# 11_-_Power_Input_and_Regulators.net
KiCad netlist of a schematic drawn in Altium Designer
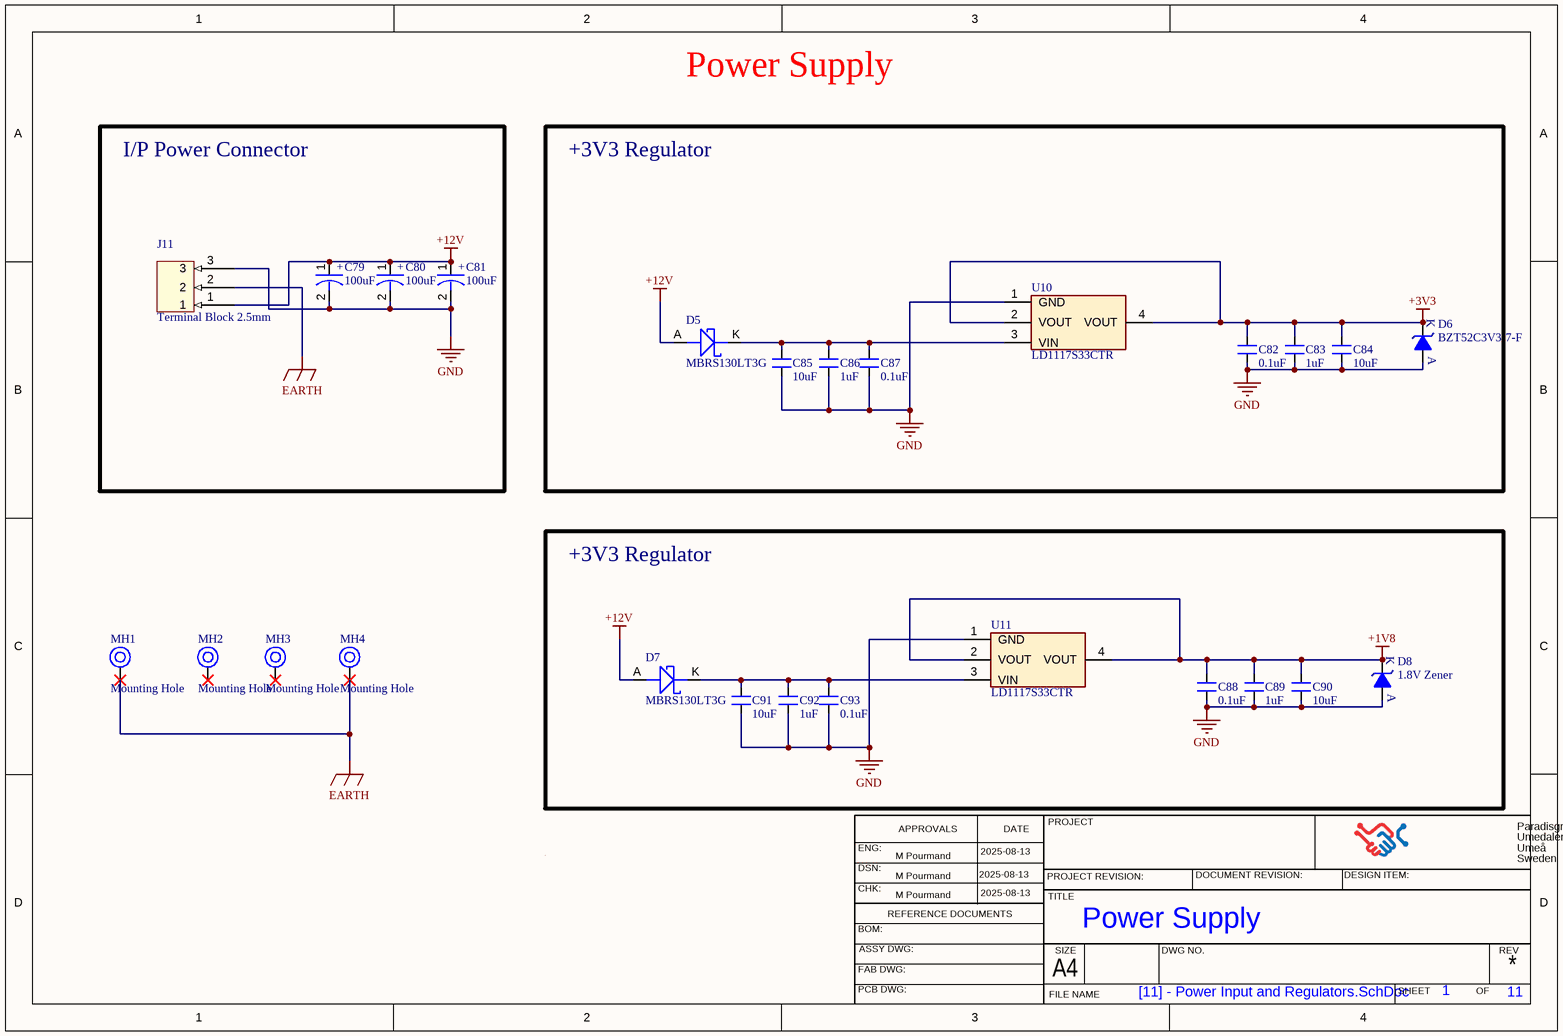
[diagram p0: [11] - Power Input and Regulators.SchDoc]

(export (version "E")
  (design (tool "Eeschema 10.0.6"))
  (components
    (comp (ref "C79")
      (value "100uF")
      (footprint "ACAP_P305_D393_H393_RAD")
      (description "100µF 50V Aluminum Polymer Capacitor Radial, Can - SMD 28mOhm 4000 Hrs @ 125°C")
      (fields
        (field (name "MANUFACTURER") "Nichicon")
        (field (name "MANUFACTURER PART NUMBER") "GYA1H101MCQ1GS")
      )
      (libsource (lib "ESTEEMPCBLIB") (part "CAP-P_100uF-50V-20%-RAD"))
    )
    (comp (ref "C80")
      (value "100uF")
      (footprint "ACAP_P305_D393_H393_RAD")
      (description "100µF 50V Aluminum Polymer Capacitor Radial, Can - SMD 28mOhm 4000 Hrs @ 125°C")
      (fields
        (field (name "MANUFACTURER") "Nichicon")
        (field (name "MANUFACTURER PART NUMBER") "GYA1H101MCQ1GS")
      )
      (libsource (lib "ESTEEMPCBLIB") (part "CAP-P_100uF-50V-20%-RAD"))
    )
    (comp (ref "C81")
      (value "100uF")
      (footprint "ACAP_P305_D393_H393_RAD")
      (description "100µF 50V Aluminum Polymer Capacitor Radial, Can - SMD 28mOhm 4000 Hrs @ 125°C")
      (fields
        (field (name "MANUFACTURER") "Nichicon")
        (field (name "MANUFACTURER PART NUMBER") "GYA1H101MCQ1GS")
      )
      (libsource (lib "ESTEEMPCBLIB") (part "CAP-P_100uF-50V-20%-RAD"))
    )
    (comp (ref "C82")
      (value "0.1uF")
      (footprint "CAP_0805")
      (description "0.1µF ±10% 50V Ceramic Capacitor X7R 0805 (2012 Metric)")
      (fields
        (field (name "MANUFACTURER") "Samsung")
        (field (name "MANUFACTURER PART NUMBER") "CL21B104KBCNNNC")
      )
      (libsource (lib "ESTEEMPCBLIB") (part "CAP_0.1uF-50V-10%-0805"))
    )
    (comp (ref "C83")
      (value "1uF")
      (footprint "CAP_0805")
      (description "1µF ±5% 50V Ceramic Capacitor X7R 0805 (2012 Metric)")
      (fields
        (field (name "MANUFACTURER") "Samsung")
        (field (name "MANUFACTURER PART NUMBER") "CC0805JKX7R9BB105")
      )
      (libsource (lib "ESTEEMPCBLIB") (part "CAP_1uF-50V-5%-0805"))
    )
    (comp (ref "C84")
      (value "10uF")
      (footprint "CAP_1206")
      (description "10µF ±10% 50V Ceramic Capacitor X7R 1206 (3216 Metric)")
      (fields
        (field (name "MANUFACTURER") "KEMET")
        (field (name "MANUFACTURER PART NUMBER") "CL31B106KBHNNNE")
      )
      (libsource (lib "ESTEEMPCBLIB") (part "CAP_10uF-50V-10%-1206"))
    )
    (comp (ref "C85")
      (value "10uF")
      (footprint "CAP_1206")
      (description "10µF ±10% 50V Ceramic Capacitor X7R 1206 (3216 Metric)")
      (fields
        (field (name "MANUFACTURER") "KEMET")
        (field (name "MANUFACTURER PART NUMBER") "CL31B106KBHNNNE")
      )
      (libsource (lib "ESTEEMPCBLIB") (part "CAP_10uF-50V-10%-1206"))
    )
    (comp (ref "C86")
      (value "1uF")
      (footprint "CAP_0805")
      (description "1µF ±5% 50V Ceramic Capacitor X7R 0805 (2012 Metric)")
      (fields
        (field (name "MANUFACTURER") "Samsung")
        (field (name "MANUFACTURER PART NUMBER") "CC0805JKX7R9BB105")
      )
      (libsource (lib "ESTEEMPCBLIB") (part "CAP_1uF-50V-5%-0805"))
    )
    (comp (ref "C87")
      (value "0.1uF")
      (footprint "CAP_0805")
      (description "0.1µF ±10% 50V Ceramic Capacitor X7R 0805 (2012 Metric)")
      (fields
        (field (name "MANUFACTURER") "Samsung")
        (field (name "MANUFACTURER PART NUMBER") "CL21B104KBCNNNC")
      )
      (libsource (lib "ESTEEMPCBLIB") (part "CAP_0.1uF-50V-10%-0805"))
    )
    (comp (ref "C88")
      (value "0.1uF")
      (footprint "CAP_0805")
      (description "0.1µF ±10% 50V Ceramic Capacitor X7R 0805 (2012 Metric)")
      (fields
        (field (name "MANUFACTURER") "Samsung")
        (field (name "MANUFACTURER PART NUMBER") "CL21B104KBCNNNC")
      )
      (libsource (lib "ESTEEMPCBLIB") (part "CAP_0.1uF-50V-10%-0805"))
    )
    (comp (ref "C89")
      (value "1uF")
      (footprint "CAP_0805")
      (description "1µF ±5% 50V Ceramic Capacitor X7R 0805 (2012 Metric)")
      (fields
        (field (name "MANUFACTURER") "Samsung")
        (field (name "MANUFACTURER PART NUMBER") "CC0805JKX7R9BB105")
      )
      (libsource (lib "ESTEEMPCBLIB") (part "CAP_1uF-50V-5%-0805"))
    )
    (comp (ref "C90")
      (value "10uF")
      (footprint "CAP_1206")
      (description "10µF ±10% 50V Ceramic Capacitor X7R 1206 (3216 Metric)")
      (fields
        (field (name "MANUFACTURER") "KEMET")
        (field (name "MANUFACTURER PART NUMBER") "CL31B106KBHNNNE")
      )
      (libsource (lib "ESTEEMPCBLIB") (part "CAP_10uF-50V-10%-1206"))
    )
    (comp (ref "C91")
      (value "10uF")
      (footprint "CAP_1206")
      (description "10µF ±10% 50V Ceramic Capacitor X7R 1206 (3216 Metric)")
      (fields
        (field (name "MANUFACTURER") "KEMET")
        (field (name "MANUFACTURER PART NUMBER") "CL31B106KBHNNNE")
      )
      (libsource (lib "ESTEEMPCBLIB") (part "CAP_10uF-50V-10%-1206"))
    )
    (comp (ref "C92")
      (value "1uF")
      (footprint "CAP_0805")
      (description "1µF ±5% 50V Ceramic Capacitor X7R 0805 (2012 Metric)")
      (fields
        (field (name "MANUFACTURER") "Samsung")
        (field (name "MANUFACTURER PART NUMBER") "CC0805JKX7R9BB105")
      )
      (libsource (lib "ESTEEMPCBLIB") (part "CAP_1uF-50V-5%-0805"))
    )
    (comp (ref "C93")
      (value "0.1uF")
      (footprint "CAP_0805")
      (description "0.1µF ±10% 50V Ceramic Capacitor X7R 0805 (2012 Metric)")
      (fields
        (field (name "MANUFACTURER") "Samsung")
        (field (name "MANUFACTURER PART NUMBER") "CL21B104KBCNNNC")
      )
      (libsource (lib "ESTEEMPCBLIB") (part "CAP_0.1uF-50V-10%-0805"))
    )
    (comp (ref "D5")
      (value "MBRS130LT3G")
      (footprint "DIO_SMB_DO-214AA")
      (description "Diode Schottky 30V 2A Surface Mount SMB")
      (fields (field (name "MANUFACTURER") "ON Semiconductor"))
      (libsource (lib "ESTEEMPCBLIB") (part "DIO-S_445mV-30V-2A-SMB"))
    )
    (comp (ref "D6")
      (value "BZT52C3V3-7-F")
      (footprint "DIO_SOD-123")
      (description "Zener Diode 3.3V 500mW ±6% Surface Mount SOD-123")
      (fields (field (name "MANUFACTURER") "Diodes Incorporated"))
      (libsource (lib "ESTEEMPCBLIB") (part "DIO-Z_3.3V-500mW-SOD123"))
    )
    (comp (ref "D7")
      (value "MBRS130LT3G")
      (footprint "DIO_SMB_DO-214AA")
      (description "Diode Schottky 30V 2A Surface Mount SMB")
      (fields (field (name "MANUFACTURER") "ON Semiconductor"))
      (libsource (lib "ESTEEMPCBLIB") (part "DIO-S_445mV-30V-2A-SMB"))
    )
    (comp (ref "D8")
      (value "1.8V Zener")
      (footprint "DIO_DO-213AB_SMD")
      (description "Zener Diode 1.8V 500mW ±5% Surface Mount DO-213AA")
      (libsource (lib "ESTEEMPCBLIB") (part "DIO-Z_1.8V-500mW-DO213AA"))
    )
    (comp (ref "J11")
      (value "Terminal Block 2.5mm")
      (footprint "CON3_100_TB_TH_ST")
      (description "3 Pins, 1 Row 2.54mm Pitch, straight Connector, male")
      (fields
        (field (name "MANUFACTURER PART NUMBER") "1725669")
        (field (name "MANUFACTURER") "Phoenix Contact")
      )
      (libsource (lib "ESTEEMPCBLIB") (part "CON-TB_3X1-100-ST-TH"))
    )
    (comp (ref "MH1")
      (value "Mounting Hole")
      (footprint "MOUNTING")
      (fields (field (name "MANUFACTURER PART NUMBER") "NA"))
      (libsource (lib "ESTEEMPCBLIB") (part "MH_3.5H_6D"))
    )
    (comp (ref "MH2")
      (value "Mounting Hole")
      (footprint "MOUNTING")
      (fields (field (name "MANUFACTURER PART NUMBER") "NA"))
      (libsource (lib "ESTEEMPCBLIB") (part "MH_3.5H_6D"))
    )
    (comp (ref "MH3")
      (value "Mounting Hole")
      (footprint "MOUNTING")
      (fields (field (name "MANUFACTURER PART NUMBER") "NA"))
      (libsource (lib "ESTEEMPCBLIB") (part "MH_3.5H_6D"))
    )
    (comp (ref "MH4")
      (value "Mounting Hole")
      (footprint "MOUNTING")
      (fields (field (name "MANUFACTURER PART NUMBER") "NA"))
      (libsource (lib "ESTEEMPCBLIB") (part "MH_3.5H_6D"))
    )
    (comp (ref "U10")
      (value "LD1117S33CTR")
      (footprint "SOT223_3")
      (description "Linear Voltage Regulator IC 1 Output 800mA SOT-223")
      (fields (field (name "MANUFACTURER") "STMicroelectronics"))
      (libsource (lib "ESTEEMPCBLIB") (part "REG_15V-3.3V-0.9A-12W-SOT223"))
    )
    (comp (ref "U11")
      (value "LD1117S33CTR")
      (footprint "SOT223_3")
      (description "Linear Voltage Regulator IC 1 Output 800mA SOT-223")
      (fields (field (name "MANUFACTURER") "STMicroelectronics"))
      (libsource (lib "ESTEEMPCBLIB") (part "REG_15V-3.3V-0.9A-12W-SOT223"))
    )
  )
  (nets
    (net (code "1") (name "+1V8") (class "Default")
      (node (ref "C88") (pin "2") (pinfunction "2_2") (pintype "passive"))
      (node (ref "C89") (pin "2") (pinfunction "2_2") (pintype "passive"))
      (node (ref "C90") (pin "2") (pinfunction "2_2") (pintype "passive"))
      (node (ref "D8") (pin "K") (pinfunction "K_K") (pintype "passive"))
      (node (ref "U11") (pin "2") (pinfunction "VOUT_2") (pintype "passive"))
      (node (ref "U11") (pin "4") (pinfunction "VOUT_4") (pintype "passive"))
    )
    (net (code "2") (name "+3V3") (class "Default")
      (node (ref "C82") (pin "2") (pinfunction "2_2") (pintype "passive"))
      (node (ref "C83") (pin "2") (pinfunction "2_2") (pintype "passive"))
      (node (ref "C84") (pin "2") (pinfunction "2_2") (pintype "passive"))
      (node (ref "D6") (pin "K") (pinfunction "K_K") (pintype "passive"))
      (node (ref "U10") (pin "2") (pinfunction "VOUT_2") (pintype "passive"))
      (node (ref "U10") (pin "4") (pinfunction "VOUT_4") (pintype "passive"))
    )
    (net (code "3") (name "+12V") (class "Default")
      (node (ref "C79") (pin "1") (pinfunction "1_1") (pintype "passive"))
      (node (ref "C80") (pin "1") (pinfunction "1_1") (pintype "passive"))
      (node (ref "C81") (pin "1") (pinfunction "1_1") (pintype "passive"))
      (node (ref "D5") (pin "A") (pinfunction "A_A") (pintype "passive"))
      (node (ref "D7") (pin "A") (pinfunction "A_A") (pintype "passive"))
      (node (ref "J11") (pin "1") (pinfunction "1_1") (pintype "input"))
    )
    (net (code "4") (name "EARTH") (class "Default")
      (node (ref "J11") (pin "2") (pinfunction "2_2") (pintype "input"))
      (node (ref "MH1") (pin "1") (pinfunction "1_1") (pintype "passive"))
      (node (ref "MH4") (pin "1") (pinfunction "1_1") (pintype "passive"))
    )
    (net (code "5") (name "GND") (class "Default")
      (node (ref "C79") (pin "2") (pinfunction "2_2") (pintype "passive"))
      (node (ref "C80") (pin "2") (pinfunction "2_2") (pintype "passive"))
      (node (ref "C81") (pin "2") (pinfunction "2_2") (pintype "passive"))
      (node (ref "C82") (pin "1") (pinfunction "1_1") (pintype "passive"))
      (node (ref "C83") (pin "1") (pinfunction "1_1") (pintype "passive"))
      (node (ref "C84") (pin "1") (pinfunction "1_1") (pintype "passive"))
      (node (ref "C85") (pin "1") (pinfunction "1_1") (pintype "passive"))
      (node (ref "C86") (pin "1") (pinfunction "1_1") (pintype "passive"))
      (node (ref "C87") (pin "1") (pinfunction "1_1") (pintype "passive"))
      (node (ref "C88") (pin "1") (pinfunction "1_1") (pintype "passive"))
      (node (ref "C89") (pin "1") (pinfunction "1_1") (pintype "passive"))
      (node (ref "C90") (pin "1") (pinfunction "1_1") (pintype "passive"))
      (node (ref "C91") (pin "1") (pinfunction "1_1") (pintype "passive"))
      (node (ref "C92") (pin "1") (pinfunction "1_1") (pintype "passive"))
      (node (ref "C93") (pin "1") (pinfunction "1_1") (pintype "passive"))
      (node (ref "D6") (pin "A") (pinfunction "A_A") (pintype "passive"))
      (node (ref "D8") (pin "A") (pinfunction "A_A") (pintype "passive"))
      (node (ref "J11") (pin "3") (pinfunction "3_3") (pintype "input"))
      (node (ref "U10") (pin "1") (pinfunction "GND_1") (pintype "passive"))
      (node (ref "U11") (pin "1") (pinfunction "GND_1") (pintype "passive"))
    )
    (net (code "6") (name "Net-(U10-VIN)") (class "Default")
      (node (ref "C85") (pin "2") (pinfunction "2_2") (pintype "passive"))
      (node (ref "C86") (pin "2") (pinfunction "2_2") (pintype "passive"))
      (node (ref "C87") (pin "2") (pinfunction "2_2") (pintype "passive"))
      (node (ref "D5") (pin "K") (pinfunction "K_K") (pintype "passive"))
      (node (ref "U10") (pin "3") (pinfunction "VIN_3") (pintype "passive"))
    )
    (net (code "7") (name "Net-(U11-VIN)") (class "Default")
      (node (ref "C91") (pin "2") (pinfunction "2_2") (pintype "passive"))
      (node (ref "C92") (pin "2") (pinfunction "2_2") (pintype "passive"))
      (node (ref "C93") (pin "2") (pinfunction "2_2") (pintype "passive"))
      (node (ref "D7") (pin "K") (pinfunction "K_K") (pintype "passive"))
      (node (ref "U11") (pin "3") (pinfunction "VIN_3") (pintype "passive"))
    )
    (net (code "8") (name "unconnected-(MH2-Pad1)") (class "Default")
      (node (ref "MH2") (pin "1") (pinfunction "1_1") (pintype "passive+no_connect"))
    )
    (net (code "9") (name "unconnected-(MH3-Pad1)") (class "Default")
      (node (ref "MH3") (pin "1") (pinfunction "1_1") (pintype "passive+no_connect"))
    )
  )
)
